# DDATN.net
KiCad netlist of a schematic drawn in Altium Designer
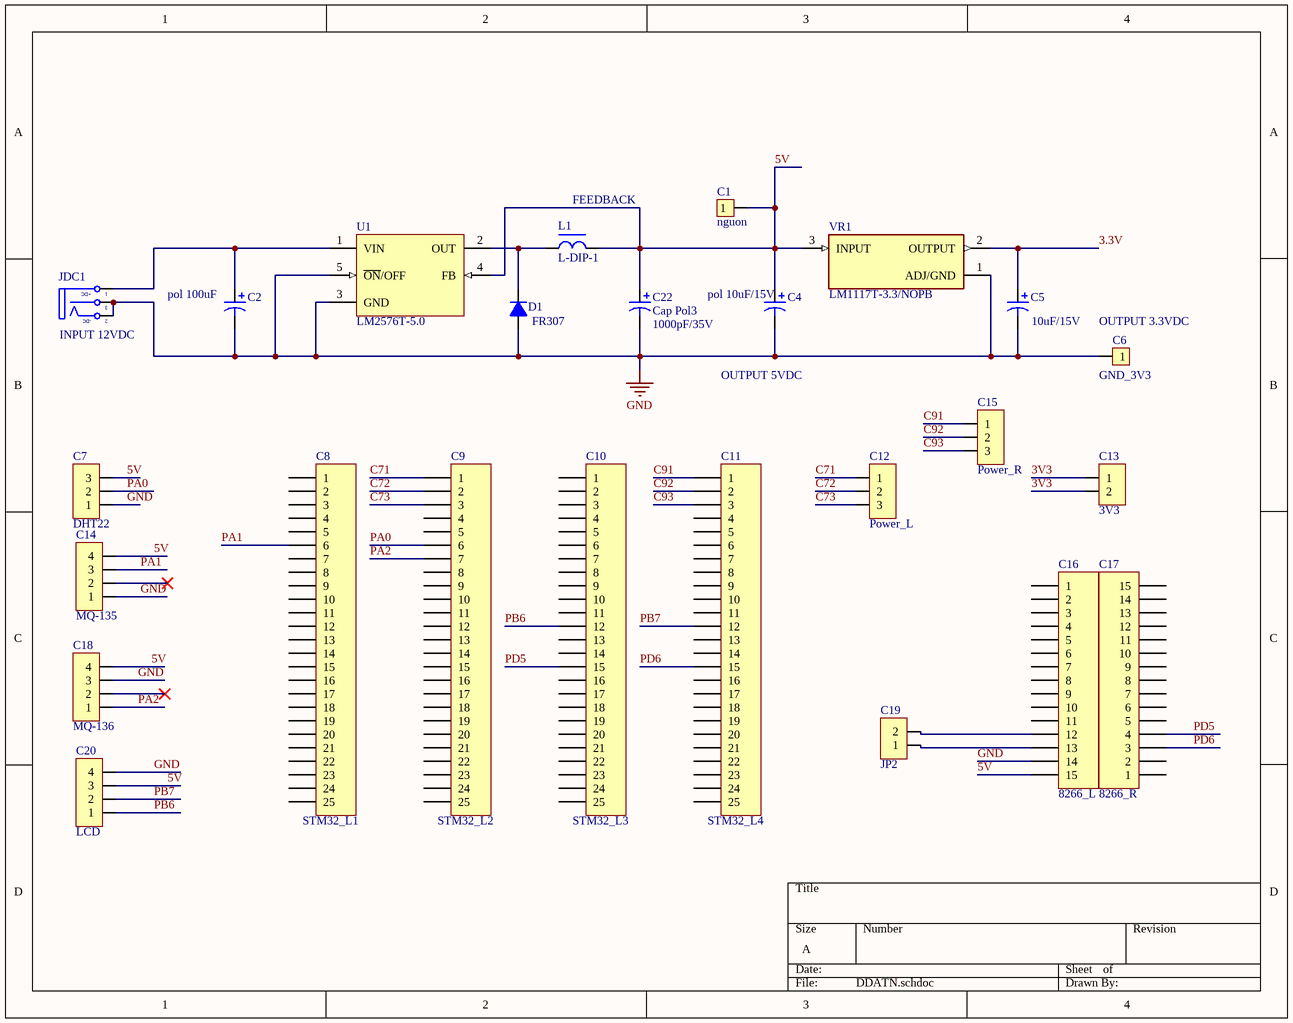
[diagram p0: DDATN.schdoc]

(export (version "E")
  (design (tool "Eeschema 10.0.6"))
  (components
    (comp (ref "C1")
      (value "nguon")
      (footprint "JP1-D1T")
      (description "WR-PHD 2.54 mm Angled Socket Header")
      (fields
        (field (name "MANUFACTURER") "Würth Elektronik eiSos GmbH")
        (field (name "PARTNO") "613002143121")
        (field (name "CREATED BY") "Karrer Zheng")
      )
      (libsource (lib "") (part "JP1_1"))
    )
    (comp (ref "C2")
      (value "pol 100uF")
      (footprint "C10mm")
      (description "Polarized Capacitor (Axial)")
      (fields (field (name "PUBLISHER") "Altium Limited"))
      (libsource (lib "My Library") (part "Cap Pol 12mm"))
    )
    (comp (ref "C4")
      (value "pol 10uF/15V")
      (footprint "C10mm")
      (description "Polarized Capacitor (Axial)")
      (fields (field (name "PUBLISHER") "Altium Limited"))
      (libsource (lib "My Library") (part "Cap Pol 12mm"))
    )
    (comp (ref "C5")
      (value "10uF/15V")
      (footprint "C10mm")
      (description "Polarized Capacitor (Axial)")
      (fields (field (name "PUBLISHER") "Altium Limited"))
      (libsource (lib "My Library") (part "Cap Pol 12mm"))
    )
    (comp (ref "C6")
      (value "GND_3V3")
      (footprint "JP1-D1T")
      (description "WR-PHD 2.54 mm Angled Socket Header")
      (fields
        (field (name "MANUFACTURER") "Würth Elektronik eiSos GmbH")
        (field (name "PARTNO") "613002143121")
        (field (name "CREATED BY") "Karrer Zheng")
      )
      (libsource (lib "LIBRARY") (part "JP1"))
    )
    (comp (ref "C7")
      (value "DHT22")
      (footprint "JP3-C1T")
      (description "WR-PHD 2.54 mm Angled Socket Header")
      (fields
        (field (name "MANUFACTURER") "Würth Elektronik eiSos GmbH")
        (field (name "PARTNO") "613003143121")
        (field (name "CREATED BY") "Karrer Zheng")
      )
      (libsource (lib "") (part "JP3_1"))
    )
    (comp (ref "C8")
      (value "STM32_L1")
      (footprint "JP25-C1T")
      (description "WR-PHD 2.54 mm Angled Socket Header")
      (fields
        (field (name "MANUFACTURER") "Würth Elektronik eiSos GmbH")
        (field (name "PARTNO") "613025143121")
        (field (name "CREATED BY") "Karrer Zheng")
      )
      (libsource (lib "LIBRARY") (part "JP25"))
    )
    (comp (ref "C9")
      (value "STM32_L2")
      (footprint "JP25-C1T")
      (description "WR-PHD 2.54 mm Angled Socket Header")
      (fields
        (field (name "MANUFACTURER") "Würth Elektronik eiSos GmbH")
        (field (name "PARTNO") "613025143121")
        (field (name "CREATED BY") "Karrer Zheng")
      )
      (libsource (lib "LIBRARY") (part "JP25"))
    )
    (comp (ref "C10")
      (value "STM32_L3")
      (footprint "JP25-C1T")
      (description "WR-PHD 2.54 mm Angled Socket Header")
      (fields
        (field (name "MANUFACTURER") "Würth Elektronik eiSos GmbH")
        (field (name "PARTNO") "613025143121")
        (field (name "CREATED BY") "Karrer Zheng")
      )
      (libsource (lib "LIBRARY") (part "JP25"))
    )
    (comp (ref "C11")
      (value "STM32_L4")
      (footprint "JP25-C1T")
      (description "WR-PHD 2.54 mm Angled Socket Header")
      (fields
        (field (name "MANUFACTURER") "Würth Elektronik eiSos GmbH")
        (field (name "PARTNO") "613025143121")
        (field (name "CREATED BY") "Karrer Zheng")
      )
      (libsource (lib "LIBRARY") (part "JP25"))
    )
    (comp (ref "C12")
      (value "Power_L")
      (footprint "JP3-C1T")
      (description "WR-PHD 2.54 mm Angled Socket Header")
      (fields
        (field (name "MANUFACTURER") "Würth Elektronik eiSos GmbH")
        (field (name "PARTNO") "613003143121")
        (field (name "CREATED BY") "Karrer Zheng")
      )
      (libsource (lib "LIBRARY") (part "JP3"))
    )
    (comp (ref "C13")
      (value "3V3")
      (footprint "JP2-C1T")
      (description "WR-PHD 2.54 mm Angled Socket Header")
      (fields
        (field (name "MANUFACTURER") "Würth Elektronik eiSos GmbH")
        (field (name "PARTNO") "613002143121")
        (field (name "CREATED BY") "Karrer Zheng")
      )
      (libsource (lib "") (part "JP2_1"))
    )
    (comp (ref "C14")
      (value "MQ-135")
      (footprint "JP4-C1T")
      (description "WR-PHD 2.54 mm Angled Socket Header")
      (fields
        (field (name "MANUFACTURER") "Würth Elektronik eiSos GmbH")
        (field (name "PARTNO") "613004143121")
        (field (name "CREATED BY") "Karrer Zheng")
      )
      (libsource (lib "LIBRARY") (part "JP4"))
    )
    (comp (ref "C15")
      (value "Power_R")
      (footprint "JP3-C1T")
      (description "WR-PHD 2.54 mm Angled Socket Header")
      (fields
        (field (name "MANUFACTURER") "Würth Elektronik eiSos GmbH")
        (field (name "PARTNO") "613003143121")
        (field (name "CREATED BY") "Karrer Zheng")
      )
      (libsource (lib "LIBRARY") (part "JP3"))
    )
    (comp (ref "C16")
      (value "8266_L")
      (footprint "JP15-C1T")
      (description "WR-PHD 2.54 mm Angled Socket Header")
      (fields
        (field (name "MANUFACTURER") "Würth Elektronik eiSos GmbH")
        (field (name "PARTNO") "613015143121")
        (field (name "CREATED BY") "Karrer Zheng")
      )
      (libsource (lib "LIBRARY") (part "JP15"))
    )
    (comp (ref "C17")
      (value "8266_R")
      (footprint "JP15-C1T")
      (description "WR-PHD 2.54 mm Angled Socket Header")
      (fields
        (field (name "MANUFACTURER") "Würth Elektronik eiSos GmbH")
        (field (name "PARTNO") "613015143121")
        (field (name "CREATED BY") "Karrer Zheng")
      )
      (libsource (lib "") (part "JP15_1"))
    )
    (comp (ref "C18")
      (value "MQ-136")
      (footprint "JP4-C1T")
      (description "WR-PHD 2.54 mm Angled Socket Header")
      (fields
        (field (name "MANUFACTURER") "Würth Elektronik eiSos GmbH")
        (field (name "PARTNO") "613004143121")
        (field (name "CREATED BY") "Karrer Zheng")
      )
      (libsource (lib "LIBRARY") (part "JP4"))
    )
    (comp (ref "C19")
      (value "JP2")
      (footprint "JP2-C1T")
      (description "WR-PHD 2.54 mm Angled Socket Header")
      (fields
        (field (name "MANUFACTURER") "Würth Elektronik eiSos GmbH")
        (field (name "PARTNO") "613002143121")
        (field (name "CREATED BY") "Karrer Zheng")
      )
      (libsource (lib "LIBRARY") (part "JP2"))
    )
    (comp (ref "C20")
      (value "LCD")
      (footprint "JP4-C1T")
      (description "WR-PHD 2.54 mm Angled Socket Header")
      (fields
        (field (name "MANUFACTURER") "Würth Elektronik eiSos GmbH")
        (field (name "PARTNO") "613004143121")
        (field (name "CREATED BY") "Karrer Zheng")
      )
      (libsource (lib "LIBRARY") (part "JP4"))
    )
    (comp (ref "C22")
      (value "Cap Pol3")
      (footprint "CP2/5")
      (description "Polarized Capacitor (Surface Mount)")
      (fields (field (name "ALTIUM_VALUE") "1000pF/35V") (field (name "PUBLISHER") "Altium Limited"))
      (libsource (lib "syhaunguyen") (part "Cap Pol3"))
    )
    (comp (ref "D1")
      (value "FR307")
      (footprint "D2A")
      (description "Diode 1A")
      (libsource (lib "syhaunguyen") (part "D1A"))
    )
    (comp (ref "JDC1")
      (value "~")
      (footprint "DC-IN")
      (description "Jac DC input")
      (libsource (lib "syhaunguyen") (part "DCIN"))
    )
    (comp (ref "L1")
      (value "L-DIP-1")
      (footprint "L-DIP-M-5.3")
      (description "Inductor")
      (libsource (lib "LIBRARY") (part "L-DIP-1"))
    )
    (comp (ref "U1")
      (value "LM2576T-5.0")
      (footprint "LM2576t")
      (description "SIMPLE SWITCHER; 3A Step-Down Voltage Regulator")
      (fields
        (field (name "MANUFACTURER") "National Semiconductor")
        (field (name "DIGIKEYPARTNUMBER") "LM2576T-5.0-ND")
        (field (name "PUBLISHER") "Altium Limited")
      )
      (libsource (lib "My Library") (part "LM2576T-5.0"))
    )
    (comp (ref "VR1")
      (value "LM1117T-3.3/NOPB")
      (footprint "TO254P1054X470X1955-3")
      (description "800-mA 15-V linear voltage regulator 3-TO-220 0 to 125")
      (fields (field (name "MF") "Texas Instruments"))
      (libsource (lib "LM1117T-3.3_NOPB") (part "LM1117T-3.3/NOPB"))
    )
  )
  (nets
    (net (code "1") (name "/3.3V") (class "Default")
      (node (ref "C5") (pin "1") (pinfunction "1_1") (pintype "passive"))
      (node (ref "VR1") (pin "2") (pinfunction "OUTPUT_2") (pintype "output"))
    )
    (net (code "2") (name "/3V3") (class "Default")
      (node (ref "C13") (pin "1") (pinfunction "1_1") (pintype "passive"))
      (node (ref "C13") (pin "2") (pinfunction "2_2") (pintype "passive"))
    )
    (net (code "3") (name "/5V") (class "Default")
      (node (ref "C1") (pin "1") (pinfunction "1_1") (pintype "passive"))
      (node (ref "C14") (pin "4") (pinfunction "4_4") (pintype "passive"))
      (node (ref "C16") (pin "15") (pinfunction "15_15") (pintype "passive"))
      (node (ref "C18") (pin "4") (pinfunction "4_4") (pintype "passive"))
      (node (ref "C20") (pin "3") (pinfunction "3_3") (pintype "passive"))
      (node (ref "C22") (pin "1") (pinfunction "1_1") (pintype "passive"))
      (node (ref "C4") (pin "1") (pinfunction "1_1") (pintype "passive"))
      (node (ref "C7") (pin "3") (pinfunction "3_3") (pintype "passive"))
      (node (ref "L1") (pin "2") (pinfunction "2_2") (pintype "passive"))
      (node (ref "U1") (pin "4") (pinfunction "FB_4") (pintype "input"))
      (node (ref "VR1") (pin "3") (pinfunction "INPUT_3") (pintype "input"))
    )
    (net (code "4") (name "/C71") (class "Default")
      (node (ref "C12") (pin "1") (pinfunction "1_1") (pintype "passive"))
      (node (ref "C9") (pin "1") (pinfunction "1_1") (pintype "passive"))
    )
    (net (code "5") (name "/C72") (class "Default")
      (node (ref "C12") (pin "2") (pinfunction "2_2") (pintype "passive"))
      (node (ref "C9") (pin "2") (pinfunction "2_2") (pintype "passive"))
    )
    (net (code "6") (name "/C73") (class "Default")
      (node (ref "C12") (pin "3") (pinfunction "3_3") (pintype "passive"))
      (node (ref "C9") (pin "3") (pinfunction "3_3") (pintype "passive"))
    )
    (net (code "7") (name "/C91") (class "Default")
      (node (ref "C11") (pin "1") (pinfunction "1_1") (pintype "passive"))
      (node (ref "C15") (pin "1") (pinfunction "1_1") (pintype "passive"))
    )
    (net (code "8") (name "/C92") (class "Default")
      (node (ref "C11") (pin "2") (pinfunction "2_2") (pintype "passive"))
      (node (ref "C15") (pin "2") (pinfunction "2_2") (pintype "passive"))
    )
    (net (code "9") (name "/C93") (class "Default")
      (node (ref "C11") (pin "3") (pinfunction "3_3") (pintype "passive"))
      (node (ref "C15") (pin "3") (pinfunction "3_3") (pintype "passive"))
    )
    (net (code "10") (name "/PA0") (class "Default")
      (node (ref "C7") (pin "2") (pinfunction "2_2") (pintype "passive"))
      (node (ref "C9") (pin "6") (pinfunction "6_6") (pintype "passive"))
    )
    (net (code "11") (name "/PA1") (class "Default")
      (node (ref "C14") (pin "3") (pinfunction "3_3") (pintype "passive"))
      (node (ref "C8") (pin "6") (pinfunction "6_6") (pintype "passive"))
    )
    (net (code "12") (name "/PA2") (class "Default")
      (node (ref "C18") (pin "1") (pinfunction "1_1") (pintype "passive"))
      (node (ref "C9") (pin "7") (pinfunction "7_7") (pintype "passive"))
    )
    (net (code "13") (name "/PB6") (class "Default")
      (node (ref "C10") (pin "12") (pinfunction "12_12") (pintype "passive"))
      (node (ref "C20") (pin "1") (pinfunction "1_1") (pintype "passive"))
    )
    (net (code "14") (name "/PB7") (class "Default")
      (node (ref "C11") (pin "12") (pinfunction "12_12") (pintype "passive"))
      (node (ref "C20") (pin "2") (pinfunction "2_2") (pintype "passive"))
    )
    (net (code "15") (name "/PD5") (class "Default")
      (node (ref "C10") (pin "15") (pinfunction "15_15") (pintype "passive"))
      (node (ref "C17") (pin "4") (pinfunction "4_4") (pintype "passive"))
    )
    (net (code "16") (name "/PD6") (class "Default")
      (node (ref "C11") (pin "15") (pinfunction "15_15") (pintype "passive"))
      (node (ref "C17") (pin "3") (pinfunction "3_3") (pintype "passive"))
    )
    (net (code "17") (name "GND") (class "Default")
      (node (ref "C14") (pin "1") (pinfunction "1_1") (pintype "passive"))
      (node (ref "C16") (pin "14") (pinfunction "14_14") (pintype "passive"))
      (node (ref "C18") (pin "3") (pinfunction "3_3") (pintype "passive"))
      (node (ref "C2") (pin "2") (pinfunction "2_2") (pintype "passive"))
      (node (ref "C20") (pin "4") (pinfunction "4_4") (pintype "passive"))
      (node (ref "C22") (pin "2") (pinfunction "2_2") (pintype "passive"))
      (node (ref "C4") (pin "2") (pinfunction "2_2") (pintype "passive"))
      (node (ref "C5") (pin "2") (pinfunction "2_2") (pintype "passive"))
      (node (ref "C6") (pin "1") (pinfunction "1_1") (pintype "passive"))
      (node (ref "C7") (pin "1") (pinfunction "1_1") (pintype "passive"))
      (node (ref "D1") (pin "1") (pinfunction "A_1") (pintype "passive"))
      (node (ref "JDC1") (pin "2") (pinfunction "TN_2") (pintype "passive"))
      (node (ref "JDC1") (pin "3") (pinfunction "S_3") (pintype "power_in"))
      (node (ref "U1") (pin "3") (pinfunction "GND_3") (pintype "power_in"))
      (node (ref "U1") (pin "5") (pinfunction "~{ON}/OFF_5") (pintype "input"))
      (node (ref "VR1") (pin "1") (pinfunction "ADJ/GND_1") (pintype "power_in"))
    )
    (net (code "18") (name "Net-(C16-Pad12)") (class "Default")
      (node (ref "C16") (pin "12") (pinfunction "12_12") (pintype "passive"))
      (node (ref "C19") (pin "2") (pinfunction "2_2") (pintype "passive"))
    )
    (net (code "19") (name "Net-(C16-Pad13)") (class "Default")
      (node (ref "C16") (pin "13") (pinfunction "13_13") (pintype "passive"))
      (node (ref "C19") (pin "1") (pinfunction "1_1") (pintype "passive"))
    )
    (net (code "20") (name "Net-(D1-K)") (class "Default")
      (node (ref "D1") (pin "2") (pinfunction "K_2") (pintype "passive"))
      (node (ref "L1") (pin "1") (pinfunction "1_1") (pintype "passive"))
      (node (ref "U1") (pin "2") (pinfunction "OUT_2") (pintype "power_in"))
    )
    (net (code "21") (name "Net-(JDC1-T)") (class "Default")
      (node (ref "C2") (pin "1") (pinfunction "1_1") (pintype "passive"))
      (node (ref "JDC1") (pin "1") (pinfunction "T_1") (pintype "passive"))
      (node (ref "U1") (pin "1") (pinfunction "VIN_1") (pintype "power_in"))
    )
    (net (code "22") (name "unconnected-(C8-Pad1)") (class "Default")
      (node (ref "C8") (pin "1") (pinfunction "1_1") (pintype "passive"))
    )
    (net (code "23") (name "unconnected-(C8-Pad2)") (class "Default")
      (node (ref "C8") (pin "2") (pinfunction "2_2") (pintype "passive"))
    )
    (net (code "24") (name "unconnected-(C8-Pad3)") (class "Default")
      (node (ref "C8") (pin "3") (pinfunction "3_3") (pintype "passive"))
    )
    (net (code "25") (name "unconnected-(C8-Pad4)") (class "Default")
      (node (ref "C8") (pin "4") (pinfunction "4_4") (pintype "passive"))
    )
    (net (code "26") (name "unconnected-(C8-Pad5)") (class "Default")
      (node (ref "C8") (pin "5") (pinfunction "5_5") (pintype "passive"))
    )
    (net (code "27") (name "unconnected-(C8-Pad7)") (class "Default")
      (node (ref "C8") (pin "7") (pinfunction "7_7") (pintype "passive"))
    )
    (net (code "28") (name "unconnected-(C8-Pad8)") (class "Default")
      (node (ref "C8") (pin "8") (pinfunction "8_8") (pintype "passive"))
    )
    (net (code "29") (name "unconnected-(C8-Pad9)") (class "Default")
      (node (ref "C8") (pin "9") (pinfunction "9_9") (pintype "passive"))
    )
    (net (code "30") (name "unconnected-(C8-Pad10)") (class "Default")
      (node (ref "C8") (pin "10") (pinfunction "10_10") (pintype "passive"))
    )
    (net (code "31") (name "unconnected-(C8-Pad11)") (class "Default")
      (node (ref "C8") (pin "11") (pinfunction "11_11") (pintype "passive"))
    )
    (net (code "32") (name "unconnected-(C8-Pad12)") (class "Default")
      (node (ref "C8") (pin "12") (pinfunction "12_12") (pintype "passive"))
    )
    (net (code "33") (name "unconnected-(C8-Pad13)") (class "Default")
      (node (ref "C8") (pin "13") (pinfunction "13_13") (pintype "passive"))
    )
    (net (code "34") (name "unconnected-(C8-Pad14)") (class "Default")
      (node (ref "C8") (pin "14") (pinfunction "14_14") (pintype "passive"))
    )
    (net (code "35") (name "unconnected-(C8-Pad15)") (class "Default")
      (node (ref "C8") (pin "15") (pinfunction "15_15") (pintype "passive"))
    )
    (net (code "36") (name "unconnected-(C8-Pad16)") (class "Default")
      (node (ref "C8") (pin "16") (pinfunction "16_16") (pintype "passive"))
    )
    (net (code "37") (name "unconnected-(C8-Pad17)") (class "Default")
      (node (ref "C8") (pin "17") (pinfunction "17_17") (pintype "passive"))
    )
    (net (code "38") (name "unconnected-(C8-Pad18)") (class "Default")
      (node (ref "C8") (pin "18") (pinfunction "18_18") (pintype "passive"))
    )
    (net (code "39") (name "unconnected-(C8-Pad19)") (class "Default")
      (node (ref "C8") (pin "19") (pinfunction "19_19") (pintype "passive"))
    )
    (net (code "40") (name "unconnected-(C8-Pad20)") (class "Default")
      (node (ref "C8") (pin "20") (pinfunction "20_20") (pintype "passive"))
    )
    (net (code "41") (name "unconnected-(C8-Pad21)") (class "Default")
      (node (ref "C8") (pin "21") (pinfunction "21_21") (pintype "passive"))
    )
    (net (code "42") (name "unconnected-(C8-Pad22)") (class "Default")
      (node (ref "C8") (pin "22") (pinfunction "22_22") (pintype "passive"))
    )
    (net (code "43") (name "unconnected-(C8-Pad23)") (class "Default")
      (node (ref "C8") (pin "23") (pinfunction "23_23") (pintype "passive"))
    )
    (net (code "44") (name "unconnected-(C8-Pad24)") (class "Default")
      (node (ref "C8") (pin "24") (pinfunction "24_24") (pintype "passive"))
    )
    (net (code "45") (name "unconnected-(C8-Pad25)") (class "Default")
      (node (ref "C8") (pin "25") (pinfunction "25_25") (pintype "passive"))
    )
    (net (code "46") (name "unconnected-(C9-Pad4)") (class "Default")
      (node (ref "C9") (pin "4") (pinfunction "4_4") (pintype "passive"))
    )
    (net (code "47") (name "unconnected-(C9-Pad5)") (class "Default")
      (node (ref "C9") (pin "5") (pinfunction "5_5") (pintype "passive"))
    )
    (net (code "48") (name "unconnected-(C9-Pad8)") (class "Default")
      (node (ref "C9") (pin "8") (pinfunction "8_8") (pintype "passive"))
    )
    (net (code "49") (name "unconnected-(C9-Pad9)") (class "Default")
      (node (ref "C9") (pin "9") (pinfunction "9_9") (pintype "passive"))
    )
    (net (code "50") (name "unconnected-(C9-Pad10)") (class "Default")
      (node (ref "C9") (pin "10") (pinfunction "10_10") (pintype "passive"))
    )
    (net (code "51") (name "unconnected-(C9-Pad11)") (class "Default")
      (node (ref "C9") (pin "11") (pinfunction "11_11") (pintype "passive"))
    )
    (net (code "52") (name "unconnected-(C9-Pad12)") (class "Default")
      (node (ref "C9") (pin "12") (pinfunction "12_12") (pintype "passive"))
    )
    (net (code "53") (name "unconnected-(C9-Pad13)") (class "Default")
      (node (ref "C9") (pin "13") (pinfunction "13_13") (pintype "passive"))
    )
    (net (code "54") (name "unconnected-(C9-Pad14)") (class "Default")
      (node (ref "C9") (pin "14") (pinfunction "14_14") (pintype "passive"))
    )
    (net (code "55") (name "unconnected-(C9-Pad15)") (class "Default")
      (node (ref "C9") (pin "15") (pinfunction "15_15") (pintype "passive"))
    )
    (net (code "56") (name "unconnected-(C9-Pad16)") (class "Default")
      (node (ref "C9") (pin "16") (pinfunction "16_16") (pintype "passive"))
    )
    (net (code "57") (name "unconnected-(C9-Pad17)") (class "Default")
      (node (ref "C9") (pin "17") (pinfunction "17_17") (pintype "passive"))
    )
    (net (code "58") (name "unconnected-(C9-Pad18)") (class "Default")
      (node (ref "C9") (pin "18") (pinfunction "18_18") (pintype "passive"))
    )
    (net (code "59") (name "unconnected-(C9-Pad19)") (class "Default")
      (node (ref "C9") (pin "19") (pinfunction "19_19") (pintype "passive"))
    )
    (net (code "60") (name "unconnected-(C9-Pad20)") (class "Default")
      (node (ref "C9") (pin "20") (pinfunction "20_20") (pintype "passive"))
    )
    (net (code "61") (name "unconnected-(C9-Pad21)") (class "Default")
      (node (ref "C9") (pin "21") (pinfunction "21_21") (pintype "passive"))
    )
    (net (code "62") (name "unconnected-(C9-Pad22)") (class "Default")
      (node (ref "C9") (pin "22") (pinfunction "22_22") (pintype "passive"))
    )
    (net (code "63") (name "unconnected-(C9-Pad23)") (class "Default")
      (node (ref "C9") (pin "23") (pinfunction "23_23") (pintype "passive"))
    )
    (net (code "64") (name "unconnected-(C9-Pad24)") (class "Default")
      (node (ref "C9") (pin "24") (pinfunction "24_24") (pintype "passive"))
    )
    (net (code "65") (name "unconnected-(C9-Pad25)") (class "Default")
      (node (ref "C9") (pin "25") (pinfunction "25_25") (pintype "passive"))
    )
    (net (code "66") (name "unconnected-(C10-Pad1)") (class "Default")
      (node (ref "C10") (pin "1") (pinfunction "1_1") (pintype "passive"))
    )
    (net (code "67") (name "unconnected-(C10-Pad2)") (class "Default")
      (node (ref "C10") (pin "2") (pinfunction "2_2") (pintype "passive"))
    )
    (net (code "68") (name "unconnected-(C10-Pad3)") (class "Default")
      (node (ref "C10") (pin "3") (pinfunction "3_3") (pintype "passive"))
    )
    (net (code "69") (name "unconnected-(C10-Pad4)") (class "Default")
      (node (ref "C10") (pin "4") (pinfunction "4_4") (pintype "passive"))
    )
    (net (code "70") (name "unconnected-(C10-Pad5)") (class "Default")
      (node (ref "C10") (pin "5") (pinfunction "5_5") (pintype "passive"))
    )
    (net (code "71") (name "unconnected-(C10-Pad6)") (class "Default")
      (node (ref "C10") (pin "6") (pinfunction "6_6") (pintype "passive"))
    )
    (net (code "72") (name "unconnected-(C10-Pad7)") (class "Default")
      (node (ref "C10") (pin "7") (pinfunction "7_7") (pintype "passive"))
    )
    (net (code "73") (name "unconnected-(C10-Pad8)") (class "Default")
      (node (ref "C10") (pin "8") (pinfunction "8_8") (pintype "passive"))
    )
    (net (code "74") (name "unconnected-(C10-Pad9)") (class "Default")
      (node (ref "C10") (pin "9") (pinfunction "9_9") (pintype "passive"))
    )
    (net (code "75") (name "unconnected-(C10-Pad10)") (class "Default")
      (node (ref "C10") (pin "10") (pinfunction "10_10") (pintype "passive"))
    )
    (net (code "76") (name "unconnected-(C10-Pad11)") (class "Default")
      (node (ref "C10") (pin "11") (pinfunction "11_11") (pintype "passive"))
    )
    (net (code "77") (name "unconnected-(C10-Pad13)") (class "Default")
      (node (ref "C10") (pin "13") (pinfunction "13_13") (pintype "passive"))
    )
    (net (code "78") (name "unconnected-(C10-Pad14)") (class "Default")
      (node (ref "C10") (pin "14") (pinfunction "14_14") (pintype "passive"))
    )
    (net (code "79") (name "unconnected-(C10-Pad16)") (class "Default")
      (node (ref "C10") (pin "16") (pinfunction "16_16") (pintype "passive"))
    )
    (net (code "80") (name "unconnected-(C10-Pad17)") (class "Default")
      (node (ref "C10") (pin "17") (pinfunction "17_17") (pintype "passive"))
    )
    (net (code "81") (name "unconnected-(C10-Pad18)") (class "Default")
      (node (ref "C10") (pin "18") (pinfunction "18_18") (pintype "passive"))
    )
    (net (code "82") (name "unconnected-(C10-Pad19)") (class "Default")
      (node (ref "C10") (pin "19") (pinfunction "19_19") (pintype "passive"))
    )
    (net (code "83") (name "unconnected-(C10-Pad20)") (class "Default")
      (node (ref "C10") (pin "20") (pinfunction "20_20") (pintype "passive"))
    )
    (net (code "84") (name "unconnected-(C10-Pad21)") (class "Default")
      (node (ref "C10") (pin "21") (pinfunction "21_21") (pintype "passive"))
    )
    (net (code "85") (name "unconnected-(C10-Pad22)") (class "Default")
      (node (ref "C10") (pin "22") (pinfunction "22_22") (pintype "passive"))
    )
    (net (code "86") (name "unconnected-(C10-Pad23)") (class "Default")
      (node (ref "C10") (pin "23") (pinfunction "23_23") (pintype "passive"))
    )
    (net (code "87") (name "unconnected-(C10-Pad24)") (class "Default")
      (node (ref "C10") (pin "24") (pinfunction "24_24") (pintype "passive"))
    )
    (net (code "88") (name "unconnected-(C10-Pad25)") (class "Default")
      (node (ref "C10") (pin "25") (pinfunction "25_25") (pintype "passive"))
    )
    (net (code "89") (name "unconnected-(C11-Pad4)") (class "Default")
      (node (ref "C11") (pin "4") (pinfunction "4_4") (pintype "passive"))
    )
    (net (code "90") (name "unconnected-(C11-Pad5)") (class "Default")
      (node (ref "C11") (pin "5") (pinfunction "5_5") (pintype "passive"))
    )
    (net (code "91") (name "unconnected-(C11-Pad6)") (class "Default")
      (node (ref "C11") (pin "6") (pinfunction "6_6") (pintype "passive"))
    )
    (net (code "92") (name "unconnected-(C11-Pad7)") (class "Default")
      (node (ref "C11") (pin "7") (pinfunction "7_7") (pintype "passive"))
    )
    (net (code "93") (name "unconnected-(C11-Pad8)") (class "Default")
      (node (ref "C11") (pin "8") (pinfunction "8_8") (pintype "passive"))
    )
    (net (code "94") (name "unconnected-(C11-Pad9)") (class "Default")
      (node (ref "C11") (pin "9") (pinfunction "9_9") (pintype "passive"))
    )
    (net (code "95") (name "unconnected-(C11-Pad10)") (class "Default")
      (node (ref "C11") (pin "10") (pinfunction "10_10") (pintype "passive"))
    )
    (net (code "96") (name "unconnected-(C11-Pad11)") (class "Default")
      (node (ref "C11") (pin "11") (pinfunction "11_11") (pintype "passive"))
    )
    (net (code "97") (name "unconnected-(C11-Pad13)") (class "Default")
      (node (ref "C11") (pin "13") (pinfunction "13_13") (pintype "passive"))
    )
    (net (code "98") (name "unconnected-(C11-Pad14)") (class "Default")
      (node (ref "C11") (pin "14") (pinfunction "14_14") (pintype "passive"))
    )
    (net (code "99") (name "unconnected-(C11-Pad16)") (class "Default")
      (node (ref "C11") (pin "16") (pinfunction "16_16") (pintype "passive"))
    )
    (net (code "100") (name "unconnected-(C11-Pad17)") (class "Default")
      (node (ref "C11") (pin "17") (pinfunction "17_17") (pintype "passive"))
    )
    (net (code "101") (name "unconnected-(C11-Pad18)") (class "Default")
      (node (ref "C11") (pin "18") (pinfunction "18_18") (pintype "passive"))
    )
    (net (code "102") (name "unconnected-(C11-Pad19)") (class "Default")
      (node (ref "C11") (pin "19") (pinfunction "19_19") (pintype "passive"))
    )
    (net (code "103") (name "unconnected-(C11-Pad20)") (class "Default")
      (node (ref "C11") (pin "20") (pinfunction "20_20") (pintype "passive"))
    )
    (net (code "104") (name "unconnected-(C11-Pad21)") (class "Default")
      (node (ref "C11") (pin "21") (pinfunction "21_21") (pintype "passive"))
    )
    (net (code "105") (name "unconnected-(C11-Pad22)") (class "Default")
      (node (ref "C11") (pin "22") (pinfunction "22_22") (pintype "passive"))
    )
    (net (code "106") (name "unconnected-(C11-Pad23)") (class "Default")
      (node (ref "C11") (pin "23") (pinfunction "23_23") (pintype "passive"))
    )
    (net (code "107") (name "unconnected-(C11-Pad24)") (class "Default")
      (node (ref "C11") (pin "24") (pinfunction "24_24") (pintype "passive"))
    )
    (net (code "108") (name "unconnected-(C11-Pad25)") (class "Default")
      (node (ref "C11") (pin "25") (pinfunction "25_25") (pintype "passive"))
    )
    (net (code "109") (name "unconnected-(C14-Pad2)") (class "Default")
      (node (ref "C14") (pin "2") (pinfunction "2_2") (pintype "passive+no_connect"))
    )
    (net (code "110") (name "unconnected-(C16-Pad1)") (class "Default")
      (node (ref "C16") (pin "1") (pinfunction "1_1") (pintype "passive"))
    )
    (net (code "111") (name "unconnected-(C16-Pad2)") (class "Default")
      (node (ref "C16") (pin "2") (pinfunction "2_2") (pintype "passive"))
    )
    (net (code "112") (name "unconnected-(C16-Pad3)") (class "Default")
      (node (ref "C16") (pin "3") (pinfunction "3_3") (pintype "passive"))
    )
    (net (code "113") (name "unconnected-(C16-Pad4)") (class "Default")
      (node (ref "C16") (pin "4") (pinfunction "4_4") (pintype "passive"))
    )
    (net (code "114") (name "unconnected-(C16-Pad5)") (class "Default")
      (node (ref "C16") (pin "5") (pinfunction "5_5") (pintype "passive"))
    )
    (net (code "115") (name "unconnected-(C16-Pad6)") (class "Default")
      (node (ref "C16") (pin "6") (pinfunction "6_6") (pintype "passive"))
    )
    (net (code "116") (name "unconnected-(C16-Pad7)") (class "Default")
      (node (ref "C16") (pin "7") (pinfunction "7_7") (pintype "passive"))
    )
    (net (code "117") (name "unconnected-(C16-Pad8)") (class "Default")
      (node (ref "C16") (pin "8") (pinfunction "8_8") (pintype "passive"))
    )
    (net (code "118") (name "unconnected-(C16-Pad9)") (class "Default")
      (node (ref "C16") (pin "9") (pinfunction "9_9") (pintype "passive"))
    )
    (net (code "119") (name "unconnected-(C16-Pad10)") (class "Default")
      (node (ref "C16") (pin "10") (pinfunction "10_10") (pintype "passive"))
    )
    (net (code "120") (name "unconnected-(C16-Pad11)") (class "Default")
      (node (ref "C16") (pin "11") (pinfunction "11_11") (pintype "passive"))
    )
    (net (code "121") (name "unconnected-(C17-Pad1)") (class "Default")
      (node (ref "C17") (pin "1") (pinfunction "1_1") (pintype "passive"))
    )
    (net (code "122") (name "unconnected-(C17-Pad2)") (class "Default")
      (node (ref "C17") (pin "2") (pinfunction "2_2") (pintype "passive"))
    )
    (net (code "123") (name "unconnected-(C17-Pad5)") (class "Default")
      (node (ref "C17") (pin "5") (pinfunction "5_5") (pintype "passive"))
    )
    (net (code "124") (name "unconnected-(C17-Pad6)") (class "Default")
      (node (ref "C17") (pin "6") (pinfunction "6_6") (pintype "passive"))
    )
    (net (code "125") (name "unconnected-(C17-Pad7)") (class "Default")
      (node (ref "C17") (pin "7") (pinfunction "7_7") (pintype "passive"))
    )
    (net (code "126") (name "unconnected-(C17-Pad8)") (class "Default")
      (node (ref "C17") (pin "8") (pinfunction "8_8") (pintype "passive"))
    )
    (net (code "127") (name "unconnected-(C17-Pad9)") (class "Default")
      (node (ref "C17") (pin "9") (pinfunction "9_9") (pintype "passive"))
    )
    (net (code "128") (name "unconnected-(C17-Pad10)") (class "Default")
      (node (ref "C17") (pin "10") (pinfunction "10_10") (pintype "passive"))
    )
    (net (code "129") (name "unconnected-(C17-Pad11)") (class "Default")
      (node (ref "C17") (pin "11") (pinfunction "11_11") (pintype "passive"))
    )
    (net (code "130") (name "unconnected-(C17-Pad12)") (class "Default")
      (node (ref "C17") (pin "12") (pinfunction "12_12") (pintype "passive"))
    )
    (net (code "131") (name "unconnected-(C17-Pad13)") (class "Default")
      (node (ref "C17") (pin "13") (pinfunction "13_13") (pintype "passive"))
    )
    (net (code "132") (name "unconnected-(C17-Pad14)") (class "Default")
      (node (ref "C17") (pin "14") (pinfunction "14_14") (pintype "passive"))
    )
    (net (code "133") (name "unconnected-(C17-Pad15)") (class "Default")
      (node (ref "C17") (pin "15") (pinfunction "15_15") (pintype "passive"))
    )
    (net (code "134") (name "unconnected-(C18-Pad2)") (class "Default")
      (node (ref "C18") (pin "2") (pinfunction "2_2") (pintype "passive+no_connect"))
    )
  )
)
